# RAM.net
KiCad netlist of a schematic drawn in Altium Designer
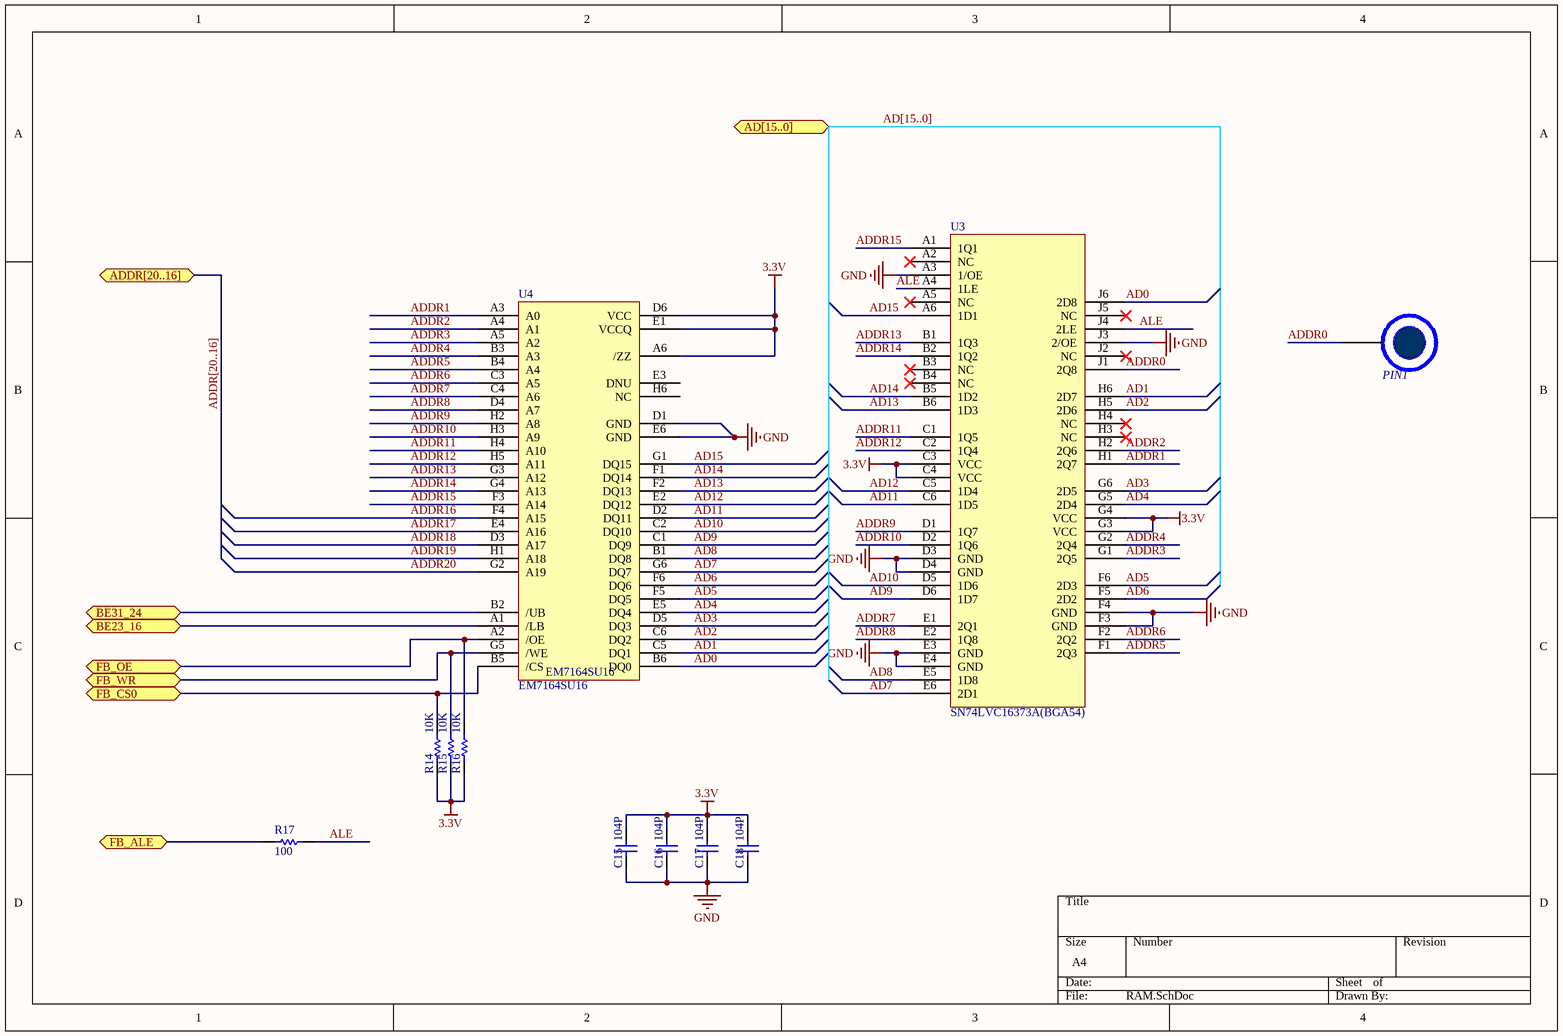
[diagram p0: RAM.SchDoc]

(export (version "E")
  (design (tool "Eeschema 10.0.6"))
  (components
    (comp (ref "C15")
      (value "104P")
      (footprint "1608[0603]")
      (description "贴片电容")
      (fields (field (name "Comment") "Cap") (field (name "PUBLISHER") "Altium Limited"))
      (libsource (lib "Sparks") (part "Cap"))
    )
    (comp (ref "C16")
      (value "104P")
      (footprint "1608[0603]")
      (description "贴片电容")
      (fields (field (name "Comment") "Cap") (field (name "PUBLISHER") "Altium Limited"))
      (libsource (lib "Sparks") (part "Cap"))
    )
    (comp (ref "C17")
      (value "104P")
      (footprint "1608[0603]")
      (description "贴片电容")
      (fields (field (name "Comment") "Cap") (field (name "PUBLISHER") "Altium Limited"))
      (libsource (lib "Sparks") (part "Cap"))
    )
    (comp (ref "C18")
      (value "104P")
      (footprint "1608[0603]")
      (description "贴片电容")
      (fields (field (name "Comment") "Cap") (field (name "PUBLISHER") "Altium Limited"))
      (libsource (lib "Sparks") (part "Cap"))
    )
    (comp (ref "PIN1") (value "PIN") (footprint "PIN") (libsource (lib "2号库") (part "PIN")))
    (comp (ref "R14")
      (value "10K")
      (footprint "1608[0603]")
      (description "贴片电阻")
      (fields (field (name "Comment") "Res") (field (name "PUBLISHER") "Altium Limited"))
      (libsource (lib "Sparks") (part "Res"))
    )
    (comp (ref "R15")
      (value "10K")
      (footprint "1608[0603]")
      (description "贴片电阻")
      (fields (field (name "Comment") "Res") (field (name "PUBLISHER") "Altium Limited"))
      (libsource (lib "Sparks") (part "Res"))
    )
    (comp (ref "R16")
      (value "10K")
      (footprint "1608[0603]")
      (description "贴片电阻")
      (fields (field (name "Comment") "Res") (field (name "PUBLISHER") "Altium Limited"))
      (libsource (lib "Sparks") (part "Res"))
    )
    (comp (ref "R17")
      (value "100")
      (footprint "1608[0603]")
      (description "贴片电阻")
      (fields (field (name "Comment") "Res") (field (name "PUBLISHER") "Altium Limited"))
      (libsource (lib "Sparks") (part "Res"))
    )
    (comp (ref "U3")
      (value "SN74LVC16373A(BGA54)")
      (footprint "BGA54C80P6X9_550X800X120")
      (libsource (lib "2号库") (part "SN74LVC16373A(BGA54)"))
    )
    (comp (ref "U4")
      (value "EM7164SU16")
      (footprint "BGA48C75P6X8_598X698X104")
      (libsource (lib "2号库") (part "EM7164SU16"))
    )
  )
  (nets
    (net (code "1") (name "/AD0") (class "Default")
      (node (ref "U3") (pin "J6") (pinfunction "2D8_J6") (pintype "passive"))
      (node (ref "U4") (pin "B6") (pinfunction "DQ0_B6") (pintype "passive"))
    )
    (net (code "2") (name "/AD1") (class "Default")
      (node (ref "U3") (pin "H6") (pinfunction "2D7_H6") (pintype "passive"))
      (node (ref "U4") (pin "C5") (pinfunction "DQ1_C5") (pintype "passive"))
    )
    (net (code "3") (name "/AD2") (class "Default")
      (node (ref "U3") (pin "H5") (pinfunction "2D6_H5") (pintype "passive"))
      (node (ref "U4") (pin "C6") (pinfunction "DQ2_C6") (pintype "passive"))
    )
    (net (code "4") (name "/AD3") (class "Default")
      (node (ref "U3") (pin "G6") (pinfunction "2D5_G6") (pintype "passive"))
      (node (ref "U4") (pin "D5") (pinfunction "DQ3_D5") (pintype "passive"))
    )
    (net (code "5") (name "/AD4") (class "Default")
      (node (ref "U3") (pin "G5") (pinfunction "2D4_G5") (pintype "passive"))
      (node (ref "U4") (pin "E5") (pinfunction "DQ4_E5") (pintype "passive"))
    )
    (net (code "6") (name "/AD5") (class "Default")
      (node (ref "U3") (pin "F6") (pinfunction "2D3_F6") (pintype "passive"))
      (node (ref "U4") (pin "F5") (pinfunction "DQ5_F5") (pintype "passive"))
    )
    (net (code "7") (name "/AD6") (class "Default")
      (node (ref "U3") (pin "F5") (pinfunction "2D2_F5") (pintype "passive"))
      (node (ref "U4") (pin "F6") (pinfunction "DQ6_F6") (pintype "passive"))
    )
    (net (code "8") (name "/AD7") (class "Default")
      (node (ref "U3") (pin "E6") (pinfunction "2D1_E6") (pintype "passive"))
      (node (ref "U4") (pin "G6") (pinfunction "DQ7_G6") (pintype "passive"))
    )
    (net (code "9") (name "/AD8") (class "Default")
      (node (ref "U3") (pin "E5") (pinfunction "1D8_E5") (pintype "passive"))
      (node (ref "U4") (pin "B1") (pinfunction "DQ8_B1") (pintype "passive"))
    )
    (net (code "10") (name "/AD9") (class "Default")
      (node (ref "U3") (pin "D6") (pinfunction "1D7_D6") (pintype "passive"))
      (node (ref "U4") (pin "C1") (pinfunction "DQ9_C1") (pintype "passive"))
    )
    (net (code "11") (name "/AD10") (class "Default")
      (node (ref "U3") (pin "D5") (pinfunction "1D6_D5") (pintype "passive"))
      (node (ref "U4") (pin "C2") (pinfunction "DQ10_C2") (pintype "passive"))
    )
    (net (code "12") (name "/AD11") (class "Default")
      (node (ref "U3") (pin "C6") (pinfunction "1D5_C6") (pintype "passive"))
      (node (ref "U4") (pin "D2") (pinfunction "DQ11_D2") (pintype "passive"))
    )
    (net (code "13") (name "/AD12") (class "Default")
      (node (ref "U3") (pin "C5") (pinfunction "1D4_C5") (pintype "passive"))
      (node (ref "U4") (pin "E2") (pinfunction "DQ12_E2") (pintype "passive"))
    )
    (net (code "14") (name "/AD13") (class "Default")
      (node (ref "U3") (pin "B6") (pinfunction "1D3_B6") (pintype "passive"))
      (node (ref "U4") (pin "F2") (pinfunction "DQ13_F2") (pintype "passive"))
    )
    (net (code "15") (name "/AD14") (class "Default")
      (node (ref "U3") (pin "B5") (pinfunction "1D2_B5") (pintype "passive"))
      (node (ref "U4") (pin "F1") (pinfunction "DQ14_F1") (pintype "passive"))
    )
    (net (code "16") (name "/AD15") (class "Default")
      (node (ref "U3") (pin "A6") (pinfunction "1D1_A6") (pintype "passive"))
      (node (ref "U4") (pin "G1") (pinfunction "DQ15_G1") (pintype "passive"))
    )
    (net (code "17") (name "/ADDR0") (class "Default")
      (node (ref "PIN1") (pin "1") (pinfunction "PIN_1") (pintype "passive"))
      (node (ref "U3") (pin "J1") (pinfunction "2Q8_J1") (pintype "passive"))
    )
    (net (code "18") (name "/ADDR1") (class "Default")
      (node (ref "U3") (pin "H1") (pinfunction "2Q7_H1") (pintype "passive"))
      (node (ref "U4") (pin "A3") (pinfunction "A0_A3") (pintype "passive"))
    )
    (net (code "19") (name "/ADDR2") (class "Default")
      (node (ref "U3") (pin "H2") (pinfunction "2Q6_H2") (pintype "passive"))
      (node (ref "U4") (pin "A4") (pinfunction "A1_A4") (pintype "passive"))
    )
    (net (code "20") (name "/ADDR3") (class "Default")
      (node (ref "U3") (pin "G1") (pinfunction "2Q5_G1") (pintype "passive"))
      (node (ref "U4") (pin "A5") (pinfunction "A2_A5") (pintype "passive"))
    )
    (net (code "21") (name "/ADDR4") (class "Default")
      (node (ref "U3") (pin "G2") (pinfunction "2Q4_G2") (pintype "passive"))
      (node (ref "U4") (pin "B3") (pinfunction "A3_B3") (pintype "passive"))
    )
    (net (code "22") (name "/ADDR5") (class "Default")
      (node (ref "U3") (pin "F1") (pinfunction "2Q3_F1") (pintype "passive"))
      (node (ref "U4") (pin "B4") (pinfunction "A4_B4") (pintype "passive"))
    )
    (net (code "23") (name "/ADDR6") (class "Default")
      (node (ref "U3") (pin "F2") (pinfunction "2Q2_F2") (pintype "passive"))
      (node (ref "U4") (pin "C3") (pinfunction "A5_C3") (pintype "passive"))
    )
    (net (code "24") (name "/ADDR7") (class "Default")
      (node (ref "U3") (pin "E1") (pinfunction "2Q1_E1") (pintype "passive"))
      (node (ref "U4") (pin "C4") (pinfunction "A6_C4") (pintype "passive"))
    )
    (net (code "25") (name "/ADDR8") (class "Default")
      (node (ref "U3") (pin "E2") (pinfunction "1Q8_E2") (pintype "passive"))
      (node (ref "U4") (pin "D4") (pinfunction "A7_D4") (pintype "passive"))
    )
    (net (code "26") (name "/ADDR9") (class "Default")
      (node (ref "U3") (pin "D1") (pinfunction "1Q7_D1") (pintype "passive"))
      (node (ref "U4") (pin "H2") (pinfunction "A8_H2") (pintype "passive"))
    )
    (net (code "27") (name "/ADDR10") (class "Default")
      (node (ref "U3") (pin "D2") (pinfunction "1Q6_D2") (pintype "passive"))
      (node (ref "U4") (pin "H3") (pinfunction "A9_H3") (pintype "passive"))
    )
    (net (code "28") (name "/ADDR11") (class "Default")
      (node (ref "U3") (pin "C1") (pinfunction "1Q5_C1") (pintype "passive"))
      (node (ref "U4") (pin "H4") (pinfunction "A10_H4") (pintype "passive"))
    )
    (net (code "29") (name "/ADDR12") (class "Default")
      (node (ref "U3") (pin "C2") (pinfunction "1Q4_C2") (pintype "passive"))
      (node (ref "U4") (pin "H5") (pinfunction "A11_H5") (pintype "passive"))
    )
    (net (code "30") (name "/ADDR13") (class "Default")
      (node (ref "U3") (pin "B1") (pinfunction "1Q3_B1") (pintype "passive"))
      (node (ref "U4") (pin "G3") (pinfunction "A12_G3") (pintype "passive"))
    )
    (net (code "31") (name "/ADDR14") (class "Default")
      (node (ref "U3") (pin "B2") (pinfunction "1Q2_B2") (pintype "passive"))
      (node (ref "U4") (pin "G4") (pinfunction "A13_G4") (pintype "passive"))
    )
    (net (code "32") (name "/ADDR15") (class "Default")
      (node (ref "U3") (pin "A1") (pinfunction "1Q1_A1") (pintype "passive"))
      (node (ref "U4") (pin "F3") (pinfunction "A14_F3") (pintype "passive"))
    )
    (net (code "33") (name "/ADDR16") (class "Default")
      (node (ref "U4") (pin "F4") (pinfunction "A15_F4") (pintype "passive"))
    )
    (net (code "34") (name "/ADDR17") (class "Default")
      (node (ref "U4") (pin "E4") (pinfunction "A16_E4") (pintype "passive"))
    )
    (net (code "35") (name "/ADDR18") (class "Default")
      (node (ref "U4") (pin "D3") (pinfunction "A17_D3") (pintype "passive"))
    )
    (net (code "36") (name "/ADDR19") (class "Default")
      (node (ref "U4") (pin "H1") (pinfunction "A18_H1") (pintype "passive"))
    )
    (net (code "37") (name "/ADDR20") (class "Default")
      (node (ref "U4") (pin "G2") (pinfunction "A19_G2") (pintype "passive"))
    )
    (net (code "40") (name "/ALE") (class "Default")
      (node (ref "R17") (pin "2") (pinfunction "2_2") (pintype "passive"))
      (node (ref "U3") (pin "A4") (pinfunction "1LE_A4") (pintype "passive"))
      (node (ref "U3") (pin "J4") (pinfunction "2LE_J4") (pintype "passive"))
    )
    (net (code "41") (name "/BE23_16") (class "Default")
      (node (ref "U4") (pin "A1") (pinfunction "/LB_A1") (pintype "passive"))
    )
    (net (code "42") (name "/BE31_24") (class "Default")
      (node (ref "U4") (pin "B2") (pinfunction "/UB_B2") (pintype "passive"))
    )
    (net (code "43") (name "/FB_ALE") (class "Default")
      (node (ref "R17") (pin "1") (pinfunction "1_1") (pintype "passive"))
    )
    (net (code "44") (name "/FB_CS0") (class "Default")
      (node (ref "R14") (pin "1") (pinfunction "1_1") (pintype "passive"))
      (node (ref "U4") (pin "B5") (pinfunction "/CS_B5") (pintype "passive"))
    )
    (net (code "45") (name "/FB_OE") (class "Default")
      (node (ref "R16") (pin "1") (pinfunction "1_1") (pintype "passive"))
      (node (ref "U4") (pin "A2") (pinfunction "/OE_A2") (pintype "passive"))
    )
    (net (code "46") (name "/FB_WR") (class "Default")
      (node (ref "R15") (pin "1") (pinfunction "1_1") (pintype "passive"))
      (node (ref "U4") (pin "G5") (pinfunction "/WE_G5") (pintype "passive"))
    )
    (net (code "47") (name "3.3V") (class "Default")
      (node (ref "C15") (pin "2") (pinfunction "2_2") (pintype "passive"))
      (node (ref "C16") (pin "2") (pinfunction "2_2") (pintype "passive"))
      (node (ref "C17") (pin "2") (pinfunction "2_2") (pintype "passive"))
      (node (ref "C18") (pin "2") (pinfunction "2_2") (pintype "passive"))
      (node (ref "R14") (pin "2") (pinfunction "2_2") (pintype "passive"))
      (node (ref "R15") (pin "2") (pinfunction "2_2") (pintype "passive"))
      (node (ref "R16") (pin "2") (pinfunction "2_2") (pintype "passive"))
      (node (ref "U3") (pin "C3") (pinfunction "VCC_C3") (pintype "passive"))
      (node (ref "U3") (pin "C4") (pinfunction "VCC_C4") (pintype "passive"))
      (node (ref "U3") (pin "G3") (pinfunction "VCC_G3") (pintype "passive"))
      (node (ref "U3") (pin "G4") (pinfunction "VCC_G4") (pintype "passive"))
      (node (ref "U4") (pin "A6") (pinfunction "/ZZ_A6") (pintype "passive"))
      (node (ref "U4") (pin "D6") (pinfunction "VCC_D6") (pintype "passive"))
      (node (ref "U4") (pin "E1") (pinfunction "VCCQ_E1") (pintype "passive"))
    )
    (net (code "48") (name "GND") (class "Default")
      (node (ref "C15") (pin "1") (pinfunction "1_1") (pintype "passive"))
      (node (ref "C16") (pin "1") (pinfunction "1_1") (pintype "passive"))
      (node (ref "C17") (pin "1") (pinfunction "1_1") (pintype "passive"))
      (node (ref "C18") (pin "1") (pinfunction "1_1") (pintype "passive"))
      (node (ref "U3") (pin "A3") (pinfunction "1/OE_A3") (pintype "passive"))
      (node (ref "U3") (pin "D3") (pinfunction "GND_D3") (pintype "passive"))
      (node (ref "U3") (pin "D4") (pinfunction "GND_D4") (pintype "passive"))
      (node (ref "U3") (pin "E3") (pinfunction "GND_E3") (pintype "passive"))
      (node (ref "U3") (pin "E4") (pinfunction "GND_E4") (pintype "passive"))
      (node (ref "U3") (pin "F3") (pinfunction "GND_F3") (pintype "passive"))
      (node (ref "U3") (pin "F4") (pinfunction "GND_F4") (pintype "passive"))
      (node (ref "U3") (pin "J3") (pinfunction "2/OE_J3") (pintype "passive"))
      (node (ref "U4") (pin "D1") (pinfunction "GND_D1") (pintype "passive"))
      (node (ref "U4") (pin "E6") (pinfunction "GND_E6") (pintype "passive"))
    )
    (net (code "49") (name "unconnected-(U3-NC-PadA2)") (class "Default")
      (node (ref "U3") (pin "A2") (pinfunction "NC_A2") (pintype "passive+no_connect"))
    )
    (net (code "50") (name "unconnected-(U3-NC-PadA5)") (class "Default")
      (node (ref "U3") (pin "A5") (pinfunction "NC_A5") (pintype "passive+no_connect"))
    )
    (net (code "51") (name "unconnected-(U3-NC-PadB3)") (class "Default")
      (node (ref "U3") (pin "B3") (pinfunction "NC_B3") (pintype "passive+no_connect"))
    )
    (net (code "52") (name "unconnected-(U3-NC-PadB4)") (class "Default")
      (node (ref "U3") (pin "B4") (pinfunction "NC_B4") (pintype "passive+no_connect"))
    )
    (net (code "53") (name "unconnected-(U3-NC-PadH3)") (class "Default")
      (node (ref "U3") (pin "H3") (pinfunction "NC_H3") (pintype "passive+no_connect"))
    )
    (net (code "54") (name "unconnected-(U3-NC-PadH4)") (class "Default")
      (node (ref "U3") (pin "H4") (pinfunction "NC_H4") (pintype "passive+no_connect"))
    )
    (net (code "55") (name "unconnected-(U3-NC-PadJ2)") (class "Default")
      (node (ref "U3") (pin "J2") (pinfunction "NC_J2") (pintype "passive+no_connect"))
    )
    (net (code "56") (name "unconnected-(U3-NC-PadJ5)") (class "Default")
      (node (ref "U3") (pin "J5") (pinfunction "NC_J5") (pintype "passive+no_connect"))
    )
    (net (code "57") (name "unconnected-(U4-DNU-PadE3)") (class "Default")
      (node (ref "U4") (pin "E3") (pinfunction "DNU_E3") (pintype "passive"))
    )
    (net (code "58") (name "unconnected-(U4-NC-PadH6)") (class "Default")
      (node (ref "U4") (pin "H6") (pinfunction "NC_H6") (pintype "passive"))
    )
  )
)
